# CON_PS2PORT_MINIDIN6F_BLACK.net
KiCad netlist of a schematic drawn in Altium Designer
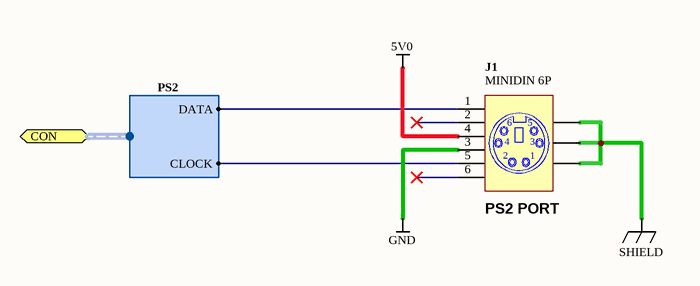
[diagram p0: CON_PS2PORT_MINIDIN6F_BLACK.SchDoc]

(export (version "E")
  (design (tool "Eeschema 10.0.6"))
  (components
    (comp (ref "J1")
      (value "MINIDIN 6P")
      (footprint "MINIDIN6PURPLE")
      (description "MINI DIN R/A F/SHLD 6P GOLD PLATED; Black")
      (libsource (lib "AltiumDesignLibrary") (part "CON-MINIDIN-6-F"))
    )
  )
  (nets
    (net (code "2") (name "/CLOCK") (class "Default")
      (node (ref "J1") (pin "5") (pinfunction "5_5") (pintype "passive"))
    )
    (net (code "3") (name "/DATA") (class "Default")
      (node (ref "J1") (pin "1") (pinfunction "1_1") (pintype "passive"))
    )
    (net (code "5") (name "5V0") (class "Default")
      (node (ref "J1") (pin "4") (pinfunction "4_4") (pintype "passive"))
    )
    (net (code "6") (name "GND") (class "Default")
      (node (ref "J1") (pin "3") (pinfunction "3_3") (pintype "passive"))
    )
    (net (code "7") (name "SHIELD") (class "Default")
      (node (ref "J1") (pin "MH1") (pinfunction "MH1_MH1") (pintype "passive"))
      (node (ref "J1") (pin "MH2") (pinfunction "MH2_MH2") (pintype "passive"))
      (node (ref "J1") (pin "MH3") (pinfunction "MH3_MH3") (pintype "passive"))
    )
    (net (code "8") (name "unconnected-(J1-Pad2)") (class "Default")
      (node (ref "J1") (pin "2") (pinfunction "2_2") (pintype "passive+no_connect"))
    )
    (net (code "9") (name "unconnected-(J1-Pad6)") (class "Default")
      (node (ref "J1") (pin "6") (pinfunction "6_6") (pintype "passive+no_connect"))
    )
  )
)
